# defmon.net
KiCad netlist of a schematic drawn in EAGLE
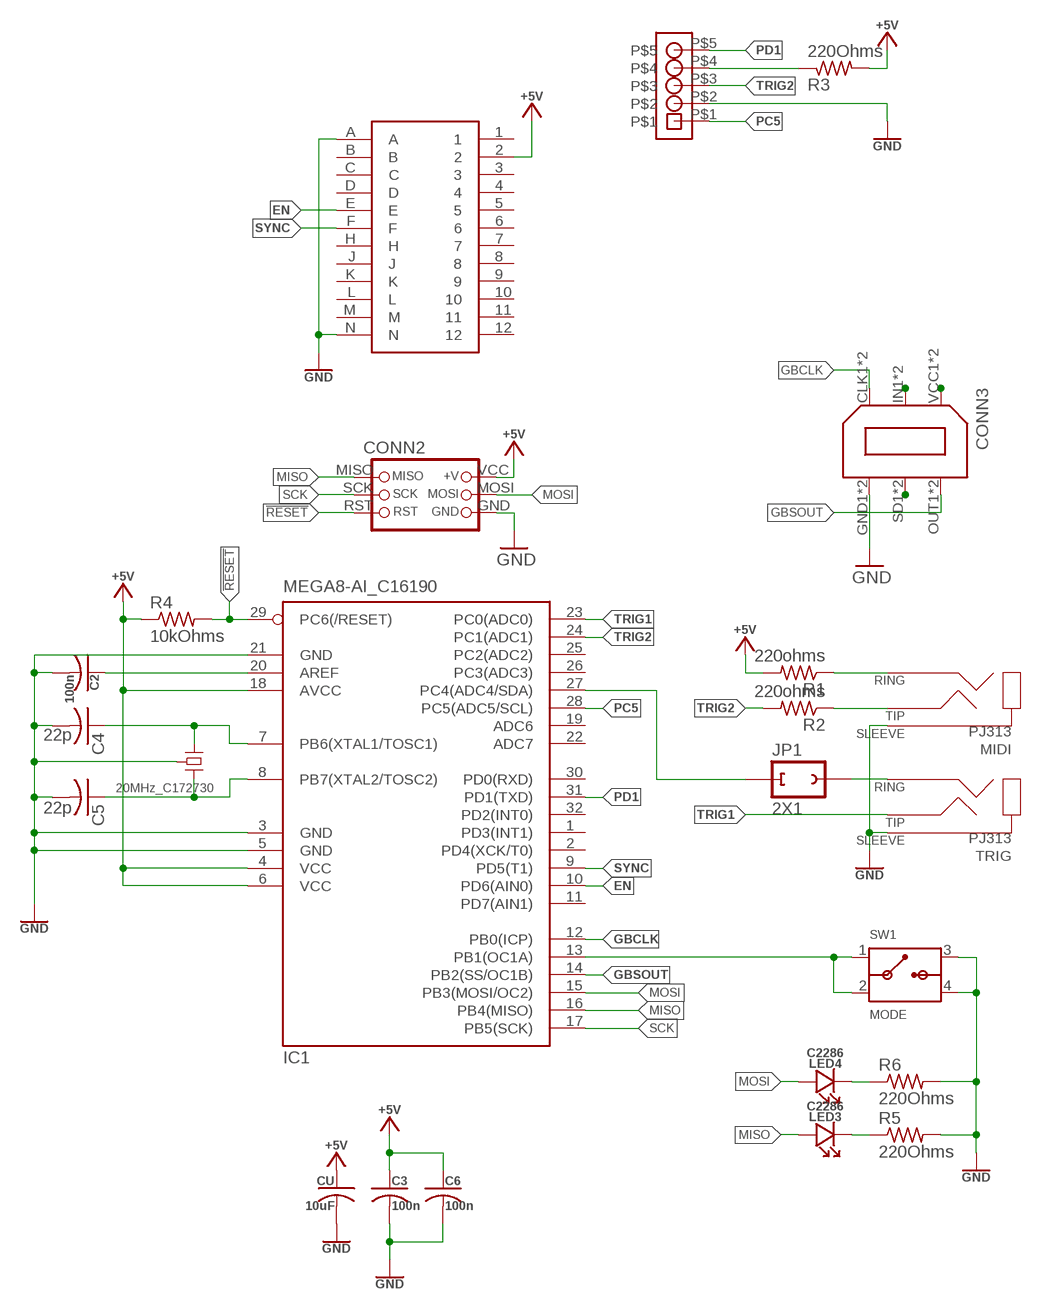
[diagram p0: schematic, sheet 1]

(export (version "E")
  (design (tool "Eeschema 10.0.6"))
  (components
    (comp (ref "C2")
      (value "100n")
      (footprint "eagle-import:C0603K")
      (libsource (lib "eagle-import") (part "C-USC0603K"))
    )
    (comp (ref "C3")
      (value "100n")
      (footprint "eagle-import:C0603K")
      (libsource (lib "eagle-import") (part "C-USC0603K"))
    )
    (comp (ref "C4")
      (value "22p")
      (footprint "eagle-import:C0603K")
      (libsource (lib "eagle-import") (part "C-USC0603K"))
    )
    (comp (ref "C5")
      (value "22p")
      (footprint "eagle-import:C0603K")
      (libsource (lib "eagle-import") (part "C-USC0603K"))
    )
    (comp (ref "C6")
      (value "100n")
      (footprint "eagle-import:C0603K")
      (libsource (lib "eagle-import") (part "C-USC0603K"))
    )
    (comp (ref "CONN2")
      (value "DNP")
      (footprint "eagle-import:ICSP_SMD_PROBE")
      (libsource (lib "eagle-import") (part "ICSP"))
    )
    (comp (ref "CONN3")
      (value "LINK_PORTFINAL")
      (footprint "eagle-import:DUAL_BAORD_LINK_FINAL")
      (libsource (lib "eagle-import") (part "LINK_PORTFINAL"))
    )
    (comp (ref "CU")
      (value "10uF")
      (footprint "eagle-import:C0603K")
      (libsource (lib "eagle-import") (part "C-USC0603K"))
    )
    (comp (ref "DIN")
      (value "1X5")
      (footprint "eagle-import:1X5")
      (libsource (lib "eagle-import") (part "1X5"))
    )
    (comp (ref "IC1")
      (value "MEGA8-AI_C16190")
      (footprint "eagle-import:TQFP32-08")
      (fields (field (name "MPN") "ATMEGA8-16AU"))
      (libsource (lib "eagle-import") (part "MEGA8-AI"))
    )
    (comp (ref "JP1")
      (value "2X1")
      (footprint "eagle-import:2X1")
      (libsource (lib "eagle-import") (part "2X1"))
    )
    (comp (ref "LED3")
      (value "C2286")
      (footprint "eagle-import:0603K")
      (libsource (lib "eagle-import") (part "0603LED"))
    )
    (comp (ref "LED4")
      (value "C2286")
      (footprint "eagle-import:0603K")
      (libsource (lib "eagle-import") (part "0603LED"))
    )
    (comp (ref "MIDI")
      (value "PJ313")
      (footprint "eagle-import:PJ313D")
      (libsource (lib "eagle-import") (part "PJ313"))
    )
    (comp (ref "Q1")
      (value "20MHz_C172730")
      (footprint "eagle-import:SX3225")
      (libsource (lib "eagle-import") (part "CRYSTAL"))
    )
    (comp (ref "R1")
      (value "220ohms")
      (footprint "eagle-import:R0603")
      (libsource (lib "eagle-import") (part "R-US_R0603"))
    )
    (comp (ref "R2")
      (value "220ohms")
      (footprint "eagle-import:R0603")
      (libsource (lib "eagle-import") (part "R-US_R0603"))
    )
    (comp (ref "R3")
      (value "220Ohms")
      (footprint "eagle-import:R0603")
      (libsource (lib "eagle-import") (part "R-US_R0603"))
    )
    (comp (ref "R4")
      (value "10kOhms")
      (footprint "eagle-import:R0603")
      (libsource (lib "eagle-import") (part "R-US_R0603"))
    )
    (comp (ref "R5")
      (value "220Ohms")
      (footprint "eagle-import:R0603")
      (libsource (lib "eagle-import") (part "R-US_R0603"))
    )
    (comp (ref "R6")
      (value "220Ohms")
      (footprint "eagle-import:R0603")
      (libsource (lib "eagle-import") (part "R-US_R0603"))
    )
    (comp (ref "SW1")
      (value "MODE")
      (footprint "eagle-import:TS5215A")
      (libsource (lib "eagle-import") (part "TACTILETS5215A"))
    )
    (comp (ref "TRIG")
      (value "PJ313")
      (footprint "eagle-import:PJ313D")
      (libsource (lib "eagle-import") (part "PJ313"))
    )
    (comp (ref "U$2")
      (value "CONNECTOR_C64UJ")
      (footprint "eagle-import:C64_USERPORT")
      (libsource (lib "eagle-import") (part "CONNECTOR_C64UJ"))
    )
  )
  (nets
    (net (code "1") (name "+5V") (class "Default")
      (node (ref "C3") (pin "1") (pinfunction "1_1") (pintype "passive"))
      (node (ref "C6") (pin "1") (pinfunction "1_1") (pintype "passive"))
      (node (ref "CONN2") (pin "VCC") (pinfunction "+V_VCC") (pintype "passive"))
      (node (ref "CU") (pin "1") (pinfunction "1_1") (pintype "passive"))
      (node (ref "IC1") (pin "18") (pinfunction "AVCC_18") (pintype "power_in"))
      (node (ref "IC1") (pin "4") (pinfunction "VCC_4") (pintype "power_in"))
      (node (ref "IC1") (pin "6") (pinfunction "VCC_6") (pintype "power_in"))
      (node (ref "R1") (pin "2") (pinfunction "2_2") (pintype "passive"))
      (node (ref "R3") (pin "2") (pinfunction "2_2") (pintype "passive"))
      (node (ref "R4") (pin "1") (pinfunction "1_1") (pintype "passive"))
      (node (ref "U$2") (pin "2") (pinfunction "2_2") (pintype "bidirectional"))
    )
    (net (code "2") (name "/~{RESET}") (class "Default")
      (node (ref "CONN2") (pin "RST") (pinfunction "RST_RST") (pintype "passive"))
      (node (ref "IC1") (pin "29") (pinfunction "PC6(/RESET)_29") (pintype "bidirectional"))
      (node (ref "R4") (pin "2") (pinfunction "2_2") (pintype "passive"))
    )
    (net (code "3") (name "EN") (class "Default")
      (node (ref "IC1") (pin "10") (pinfunction "PD6(AIN0)_10") (pintype "bidirectional"))
      (node (ref "U$2") (pin "E") (pinfunction "E_E") (pintype "bidirectional"))
    )
    (net (code "4") (name "GBCLK") (class "Default")
      (node (ref "CONN3") (pin "CLK1") (pinfunction "CLK_CLK1") (pintype "bidirectional"))
      (node (ref "CONN3") (pin "CLK2") (pinfunction "CLK_CLK2") (pintype "bidirectional"))
      (node (ref "IC1") (pin "12") (pinfunction "PB0(ICP)_12") (pintype "bidirectional"))
    )
    (net (code "5") (name "GBSOUT") (class "Default")
      (node (ref "CONN3") (pin "OUT1") (pinfunction "OUT_OUT1") (pintype "bidirectional"))
      (node (ref "CONN3") (pin "OUT2") (pinfunction "OUT_OUT2") (pintype "bidirectional"))
      (node (ref "IC1") (pin "14") (pinfunction "PB2(SS/OC1B)_14") (pintype "bidirectional"))
    )
    (net (code "6") (name "GND") (class "Default")
      (node (ref "C2") (pin "2") (pinfunction "2_2") (pintype "passive"))
      (node (ref "C3") (pin "2") (pinfunction "2_2") (pintype "passive"))
      (node (ref "C4") (pin "2") (pinfunction "2_2") (pintype "passive"))
      (node (ref "C5") (pin "2") (pinfunction "2_2") (pintype "passive"))
      (node (ref "C6") (pin "2") (pinfunction "2_2") (pintype "passive"))
      (node (ref "CONN2") (pin "GND") (pinfunction "GND_GND") (pintype "passive"))
      (node (ref "CONN3") (pin "GND1") (pinfunction "GND_GND1") (pintype "bidirectional"))
      (node (ref "CONN3") (pin "GND2") (pinfunction "GND_GND2") (pintype "bidirectional"))
      (node (ref "CU") (pin "2") (pinfunction "2_2") (pintype "passive"))
      (node (ref "DIN") (pin "P$2") (pinfunction "P$2_P$2") (pintype "bidirectional"))
      (node (ref "IC1") (pin "21") (pinfunction "GND_21") (pintype "power_in"))
      (node (ref "IC1") (pin "3") (pinfunction "GND_3") (pintype "power_in"))
      (node (ref "IC1") (pin "5") (pinfunction "GND_5") (pintype "power_in"))
      (node (ref "MIDI") (pin "2") (pinfunction "2_2") (pintype "bidirectional"))
      (node (ref "MIDI") (pin "22") (pinfunction "2_22") (pintype "bidirectional"))
      (node (ref "Q1") (pin "2") (pinfunction "GND_2") (pintype "bidirectional"))
      (node (ref "Q1") (pin "4") (pinfunction "GND_4") (pintype "bidirectional"))
      (node (ref "R5") (pin "2") (pinfunction "2_2") (pintype "passive"))
      (node (ref "R6") (pin "2") (pinfunction "2_2") (pintype "passive"))
      (node (ref "SW1") (pin "3") (pinfunction "B1_3") (pintype "bidirectional"))
      (node (ref "SW1") (pin "4") (pinfunction "B2_4") (pintype "bidirectional"))
      (node (ref "TRIG") (pin "2") (pinfunction "2_2") (pintype "bidirectional"))
      (node (ref "TRIG") (pin "22") (pinfunction "2_22") (pintype "bidirectional"))
      (node (ref "U$2") (pin "A") (pinfunction "A_A") (pintype "bidirectional"))
      (node (ref "U$2") (pin "N") (pinfunction "N_N") (pintype "bidirectional"))
    )
    (net (code "7") (name "MISO") (class "Default")
      (node (ref "CONN2") (pin "MISO") (pinfunction "MISO_MISO") (pintype "passive"))
      (node (ref "IC1") (pin "16") (pinfunction "PB4(MISO)_16") (pintype "bidirectional"))
      (node (ref "LED3") (pin "A") (pinfunction "A_A") (pintype "bidirectional"))
    )
    (net (code "8") (name "MOSI") (class "Default")
      (node (ref "CONN2") (pin "MOSI") (pinfunction "MOSI_MOSI") (pintype "passive"))
      (node (ref "IC1") (pin "15") (pinfunction "PB3(MOSI/OC2)_15") (pintype "bidirectional"))
      (node (ref "LED4") (pin "A") (pinfunction "A_A") (pintype "bidirectional"))
    )
    (net (code "9") (name "Net-(CONN3-+5V-PadVCC1)") (class "Default")
      (node (ref "CONN3") (pin "VCC1") (pinfunction "+5V_VCC1") (pintype "bidirectional"))
      (node (ref "CONN3") (pin "VCC2") (pinfunction "+5V_VCC2") (pintype "bidirectional"))
    )
    (net (code "10") (name "Net-(CONN3-IN-PadIN1)") (class "Default")
      (node (ref "CONN3") (pin "IN1") (pinfunction "IN_IN1") (pintype "bidirectional"))
      (node (ref "CONN3") (pin "IN2") (pinfunction "IN_IN2") (pintype "bidirectional"))
    )
    (net (code "11") (name "Net-(CONN3-SD-PadSD1)") (class "Default")
      (node (ref "CONN3") (pin "SD1") (pinfunction "SD_SD1") (pintype "bidirectional"))
      (node (ref "CONN3") (pin "SD2") (pinfunction "SD_SD2") (pintype "bidirectional"))
    )
    (net (code "12") (name "Net-(DIN-PadP$4)") (class "Default")
      (node (ref "DIN") (pin "P$4") (pinfunction "P$4_P$4") (pintype "bidirectional"))
      (node (ref "R3") (pin "1") (pinfunction "1_1") (pintype "passive"))
    )
    (net (code "13") (name "Net-(IC1-AREF)") (class "Default")
      (node (ref "C2") (pin "1") (pinfunction "1_1") (pintype "passive"))
      (node (ref "IC1") (pin "20") (pinfunction "AREF_20") (pintype "passive"))
    )
    (net (code "14") (name "Net-(IC1-PB1(OC1A))") (class "Default")
      (node (ref "IC1") (pin "13") (pinfunction "PB1(OC1A)_13") (pintype "bidirectional"))
      (node (ref "SW1") (pin "1") (pinfunction "A1_1") (pintype "bidirectional"))
      (node (ref "SW1") (pin "2") (pinfunction "A2_2") (pintype "bidirectional"))
    )
    (net (code "15") (name "Net-(IC1-PB6(XTAL1{slash}TOSC1))") (class "Default")
      (node (ref "C4") (pin "1") (pinfunction "1_1") (pintype "passive"))
      (node (ref "IC1") (pin "7") (pinfunction "PB6(XTAL1/TOSC1)_7") (pintype "bidirectional"))
      (node (ref "Q1") (pin "3") (pinfunction "X1_3") (pintype "bidirectional"))
    )
    (net (code "16") (name "Net-(IC1-PB7(XTAL2{slash}TOSC2))") (class "Default")
      (node (ref "C5") (pin "1") (pinfunction "1_1") (pintype "passive"))
      (node (ref "IC1") (pin "8") (pinfunction "PB7(XTAL2/TOSC2)_8") (pintype "bidirectional"))
      (node (ref "Q1") (pin "1") (pinfunction "X2_1") (pintype "bidirectional"))
    )
    (net (code "17") (name "Net-(IC1-PC4(ADC4{slash}SDA))") (class "Default")
      (node (ref "IC1") (pin "27") (pinfunction "PC4(ADC4/SDA)_27") (pintype "bidirectional"))
      (node (ref "JP1") (pin "P$1") (pinfunction "1_P$1") (pintype "passive"))
    )
    (net (code "18") (name "Net-(JP1-2)") (class "Default")
      (node (ref "JP1") (pin "P$2") (pinfunction "2_P$2") (pintype "passive"))
      (node (ref "TRIG") (pin "3") (pinfunction "3_3") (pintype "bidirectional"))
    )
    (net (code "19") (name "Net-(LED3-PadC)") (class "Default")
      (node (ref "LED3") (pin "C") (pinfunction "C_C") (pintype "bidirectional"))
      (node (ref "R5") (pin "1") (pinfunction "1_1") (pintype "passive"))
    )
    (net (code "20") (name "Net-(LED4-PadC)") (class "Default")
      (node (ref "LED4") (pin "C") (pinfunction "C_C") (pintype "bidirectional"))
      (node (ref "R6") (pin "1") (pinfunction "1_1") (pintype "passive"))
    )
    (net (code "21") (name "Net-(MIDI-4-Pad44)") (class "Default")
      (node (ref "MIDI") (pin "4") (pinfunction "4_4") (pintype "bidirectional"))
      (node (ref "MIDI") (pin "44") (pinfunction "4_44") (pintype "bidirectional"))
      (node (ref "R2") (pin "1") (pinfunction "1_1") (pintype "passive"))
    )
    (net (code "22") (name "Net-(MIDI-Pad3)") (class "Default")
      (node (ref "MIDI") (pin "3") (pinfunction "3_3") (pintype "bidirectional"))
      (node (ref "R1") (pin "1") (pinfunction "1_1") (pintype "passive"))
    )
    (net (code "23") (name "PC5") (class "Default")
      (node (ref "DIN") (pin "P$1") (pinfunction "P$1_P$1") (pintype "bidirectional"))
      (node (ref "IC1") (pin "28") (pinfunction "PC5(ADC5/SCL)_28") (pintype "bidirectional"))
    )
    (net (code "24") (name "PD1") (class "Default")
      (node (ref "DIN") (pin "P$5") (pinfunction "P$5_P$5") (pintype "bidirectional"))
      (node (ref "IC1") (pin "31") (pinfunction "PD1(TXD)_31") (pintype "bidirectional"))
    )
    (net (code "25") (name "SCK") (class "Default")
      (node (ref "CONN2") (pin "SCK") (pinfunction "SCK_SCK") (pintype "passive"))
      (node (ref "IC1") (pin "17") (pinfunction "PB5(SCK)_17") (pintype "bidirectional"))
    )
    (net (code "26") (name "SYNC") (class "Default")
      (node (ref "IC1") (pin "9") (pinfunction "PD5(T1)_9") (pintype "bidirectional"))
      (node (ref "U$2") (pin "F") (pinfunction "F_F") (pintype "bidirectional"))
    )
    (net (code "27") (name "TRIG1") (class "Default")
      (node (ref "IC1") (pin "23") (pinfunction "PC0(ADC0)_23") (pintype "bidirectional"))
      (node (ref "TRIG") (pin "4") (pinfunction "4_4") (pintype "bidirectional"))
      (node (ref "TRIG") (pin "44") (pinfunction "4_44") (pintype "bidirectional"))
    )
    (net (code "28") (name "TRIG2") (class "Default")
      (node (ref "DIN") (pin "P$3") (pinfunction "P$3_P$3") (pintype "bidirectional"))
      (node (ref "IC1") (pin "24") (pinfunction "PC1(ADC1)_24") (pintype "bidirectional"))
      (node (ref "R2") (pin "2") (pinfunction "2_2") (pintype "passive"))
    )
    (net (code "29") (name "unconnected-(IC1-ADC6-Pad19)") (class "Default")
      (node (ref "IC1") (pin "19") (pinfunction "ADC6_19") (pintype "bidirectional"))
    )
    (net (code "30") (name "unconnected-(IC1-ADC7-Pad22)") (class "Default")
      (node (ref "IC1") (pin "22") (pinfunction "ADC7_22") (pintype "bidirectional"))
    )
    (net (code "31") (name "unconnected-(IC1-PC2(ADC2)-Pad25)") (class "Default")
      (node (ref "IC1") (pin "25") (pinfunction "PC2(ADC2)_25") (pintype "bidirectional"))
    )
    (net (code "32") (name "unconnected-(IC1-PC3(ADC3)-Pad26)") (class "Default")
      (node (ref "IC1") (pin "26") (pinfunction "PC3(ADC3)_26") (pintype "bidirectional"))
    )
    (net (code "33") (name "unconnected-(IC1-PD0(RXD)-Pad30)") (class "Default")
      (node (ref "IC1") (pin "30") (pinfunction "PD0(RXD)_30") (pintype "bidirectional"))
    )
    (net (code "34") (name "unconnected-(IC1-PD2(INT0)-Pad32)") (class "Default")
      (node (ref "IC1") (pin "32") (pinfunction "PD2(INT0)_32") (pintype "bidirectional"))
    )
    (net (code "35") (name "unconnected-(IC1-PD3(INT1)-Pad1)") (class "Default")
      (node (ref "IC1") (pin "1") (pinfunction "PD3(INT1)_1") (pintype "bidirectional"))
    )
    (net (code "36") (name "unconnected-(IC1-PD4(XCK{slash}T0)-Pad2)") (class "Default")
      (node (ref "IC1") (pin "2") (pinfunction "PD4(XCK/T0)_2") (pintype "bidirectional"))
    )
    (net (code "37") (name "unconnected-(IC1-PD7(AIN1)-Pad11)") (class "Default")
      (node (ref "IC1") (pin "11") (pinfunction "PD7(AIN1)_11") (pintype "bidirectional"))
    )
    (net (code "38") (name "unconnected-(U$2-Pad1)") (class "Default")
      (node (ref "U$2") (pin "1") (pinfunction "1_1") (pintype "bidirectional"))
    )
    (net (code "39") (name "unconnected-(U$2-Pad3)") (class "Default")
      (node (ref "U$2") (pin "3") (pinfunction "3_3") (pintype "bidirectional"))
    )
    (net (code "40") (name "unconnected-(U$2-Pad4)") (class "Default")
      (node (ref "U$2") (pin "4") (pinfunction "4_4") (pintype "bidirectional"))
    )
    (net (code "41") (name "unconnected-(U$2-Pad5)") (class "Default")
      (node (ref "U$2") (pin "5") (pinfunction "5_5") (pintype "bidirectional"))
    )
    (net (code "42") (name "unconnected-(U$2-Pad6)") (class "Default")
      (node (ref "U$2") (pin "6") (pinfunction "6_6") (pintype "bidirectional"))
    )
    (net (code "43") (name "unconnected-(U$2-Pad7)") (class "Default")
      (node (ref "U$2") (pin "7") (pinfunction "7_7") (pintype "bidirectional"))
    )
    (net (code "44") (name "unconnected-(U$2-Pad8)") (class "Default")
      (node (ref "U$2") (pin "8") (pinfunction "8_8") (pintype "bidirectional"))
    )
    (net (code "45") (name "unconnected-(U$2-Pad9)") (class "Default")
      (node (ref "U$2") (pin "9") (pinfunction "9_9") (pintype "bidirectional"))
    )
    (net (code "46") (name "unconnected-(U$2-Pad10)") (class "Default")
      (node (ref "U$2") (pin "10") (pinfunction "10_10") (pintype "bidirectional"))
    )
    (net (code "47") (name "unconnected-(U$2-Pad11)") (class "Default")
      (node (ref "U$2") (pin "11") (pinfunction "11_11") (pintype "bidirectional"))
    )
    (net (code "48") (name "unconnected-(U$2-Pad12)") (class "Default")
      (node (ref "U$2") (pin "12") (pinfunction "12_12") (pintype "bidirectional"))
    )
    (net (code "49") (name "unconnected-(U$2-PadB)") (class "Default")
      (node (ref "U$2") (pin "B") (pinfunction "B_B") (pintype "bidirectional"))
    )
    (net (code "50") (name "unconnected-(U$2-PadC)") (class "Default")
      (node (ref "U$2") (pin "C") (pinfunction "C_C") (pintype "bidirectional"))
    )
    (net (code "51") (name "unconnected-(U$2-PadD)") (class "Default")
      (node (ref "U$2") (pin "D") (pinfunction "D_D") (pintype "bidirectional"))
    )
    (net (code "52") (name "unconnected-(U$2-PadH)") (class "Default")
      (node (ref "U$2") (pin "H") (pinfunction "H_H") (pintype "bidirectional"))
    )
    (net (code "53") (name "unconnected-(U$2-PadJ)") (class "Default")
      (node (ref "U$2") (pin "J") (pinfunction "J_J") (pintype "bidirectional"))
    )
    (net (code "54") (name "unconnected-(U$2-PadK)") (class "Default")
      (node (ref "U$2") (pin "K") (pinfunction "K_K") (pintype "bidirectional"))
    )
    (net (code "55") (name "unconnected-(U$2-PadL)") (class "Default")
      (node (ref "U$2") (pin "L") (pinfunction "L_L") (pintype "bidirectional"))
    )
    (net (code "56") (name "unconnected-(U$2-PadM)") (class "Default")
      (node (ref "U$2") (pin "M") (pinfunction "M_M") (pintype "bidirectional"))
    )
  )
)
